# schematics.net
KiCad netlist of a schematic drawn in EAGLE
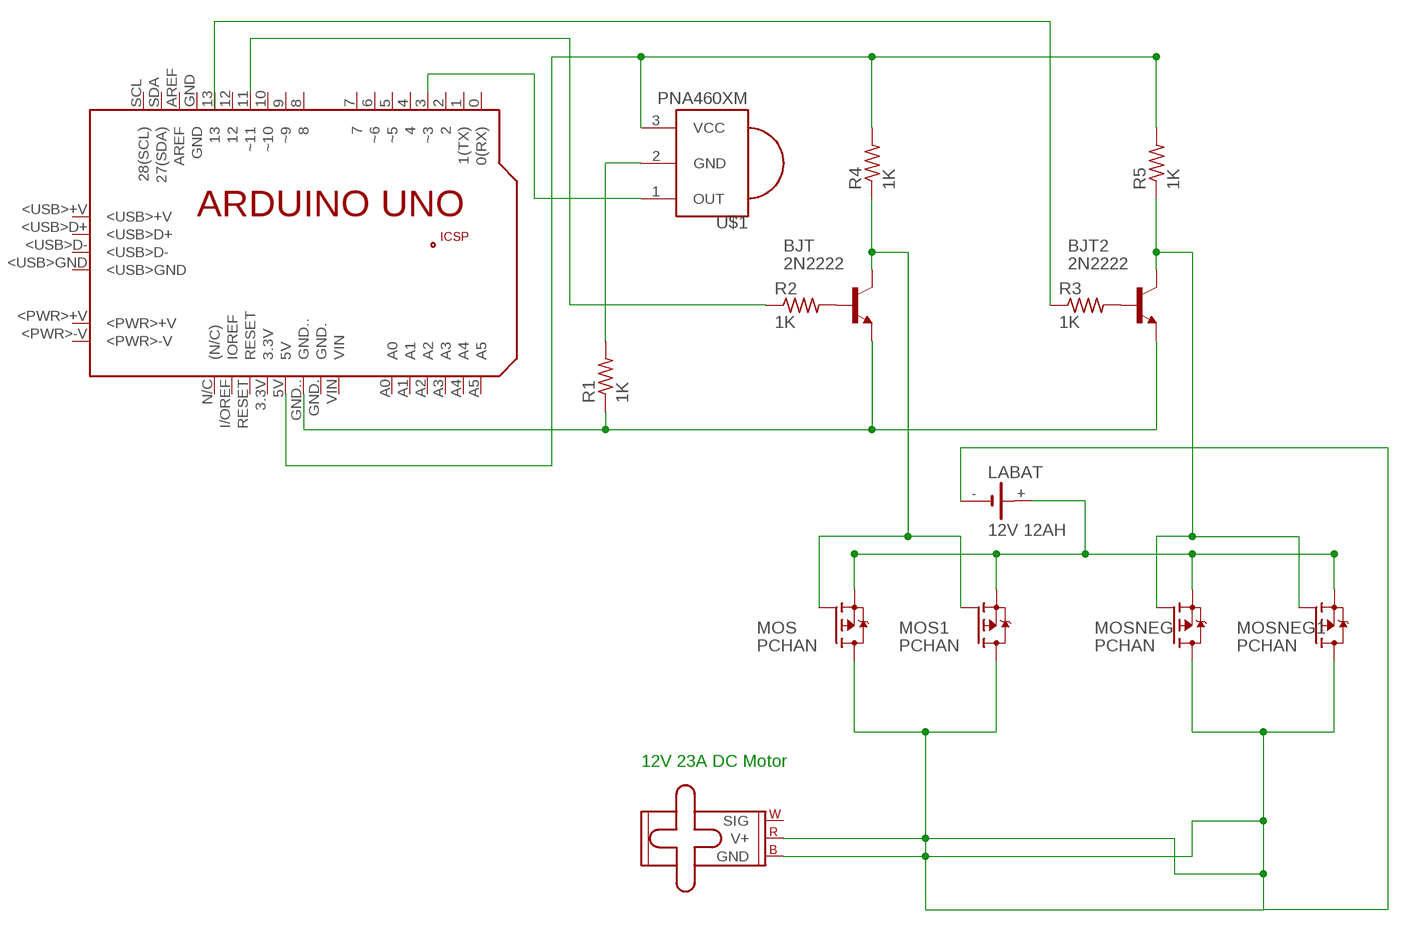
[diagram p0: schematic, sheet 1]

(export (version "E")
  (design (tool "Eeschema 10.0.6"))
  (components
    (comp (ref "BJT")
      (value "2N2222")
      (footprint "eagle-import:TO92-EBC-OVAL")
      (libsource (lib "eagle-import") (part "2N2222"))
    )
    (comp (ref "BJT2")
      (value "2N2222")
      (footprint "eagle-import:TO92-EBC-OVAL")
      (libsource (lib "eagle-import") (part "2N2222"))
    )
    (comp (ref "DCMOTOR")
      (value "12V 23A")
      (footprint "eagle-import:1X03")
      (libsource (lib "eagle-import") (part "SMALL_SERVO"))
    )
    (comp (ref "LABAT")
      (value "12V 12AH")
      (footprint "eagle-import:SL-160AA_PR")
      (libsource (lib "eagle-import") (part "SL-160AA/PR"))
    )
    (comp (ref "MOS")
      (value "PCHAN")
      (footprint "eagle-import:TO252")
      (libsource (lib "eagle-import") (part "FDD4141TO252"))
    )
    (comp (ref "MOS1")
      (value "PCHAN")
      (footprint "eagle-import:TO252")
      (libsource (lib "eagle-import") (part "FDD4141TO252"))
    )
    (comp (ref "MOSNEG")
      (value "PCHAN")
      (footprint "eagle-import:TO252")
      (libsource (lib "eagle-import") (part "FDD4141TO252"))
    )
    (comp (ref "MOSNEG1")
      (value "PCHAN")
      (footprint "eagle-import:TO252")
      (libsource (lib "eagle-import") (part "FDD4141TO252"))
    )
    (comp (ref "PCB1")
      (value "ARDUINO_UNO")
      (footprint "eagle-import:ARDUINO_UNO")
      (libsource (lib "eagle-import") (part "ARDUINO_UNO"))
    )
    (comp (ref "R1")
      (value "1K")
      (footprint "eagle-import:0207_7")
      (libsource (lib "eagle-import") (part "R-US_0207/7"))
    )
    (comp (ref "R2")
      (value "1K")
      (footprint "eagle-import:0207_7")
      (libsource (lib "eagle-import") (part "R-US_0207/7"))
    )
    (comp (ref "R3")
      (value "1K")
      (footprint "eagle-import:0207_7")
      (libsource (lib "eagle-import") (part "R-US_0207/7"))
    )
    (comp (ref "R4")
      (value "1K")
      (footprint "eagle-import:0207_7")
      (libsource (lib "eagle-import") (part "R-US_0207/7"))
    )
    (comp (ref "R5")
      (value "1K")
      (footprint "eagle-import:0207_7")
      (libsource (lib "eagle-import") (part "R-US_0207/7"))
    )
    (comp (ref "U$1")
      (value "PNA460XM")
      (footprint "eagle-import:PNA460XM")
      (libsource (lib "eagle-import") (part "PNA460XM"))
    )
  )
  (nets
    (net (code "1") (name "Net-(BJT-PadB)") (class "Default")
      (node (ref "BJT") (pin "B") (pinfunction "B_B") (pintype "passive"))
      (node (ref "R2") (pin "2") (pinfunction "2_2") (pintype "passive"))
    )
    (net (code "2") (name "Net-(BJT-PadE)") (class "Default")
      (node (ref "BJT") (pin "E") (pinfunction "E_E") (pintype "passive"))
      (node (ref "BJT2") (pin "E") (pinfunction "E_E") (pintype "passive"))
      (node (ref "PCB1") (pin "GND..") (pinfunction "GND.._GND..") (pintype "bidirectional"))
      (node (ref "R1") (pin "1") (pinfunction "1_1") (pintype "passive"))
    )
    (net (code "3") (name "Net-(BJT2-PadB)") (class "Default")
      (node (ref "BJT2") (pin "B") (pinfunction "B_B") (pintype "passive"))
      (node (ref "R3") (pin "2") (pinfunction "2_2") (pintype "passive"))
    )
    (net (code "4") (name "Net-(DCMOTOR-GND)") (class "Default")
      (node (ref "DCMOTOR") (pin "2") (pinfunction "V+_2") (pintype "bidirectional"))
      (node (ref "DCMOTOR") (pin "3") (pinfunction "GND_3") (pintype "bidirectional"))
      (node (ref "LABAT") (pin "-") (pinfunction "-_-") (pintype "passive"))
      (node (ref "MOS") (pin "3") (pinfunction "D_3") (pintype "passive"))
      (node (ref "MOS1") (pin "3") (pinfunction "D_3") (pintype "passive"))
      (node (ref "MOSNEG") (pin "3") (pinfunction "D_3") (pintype "passive"))
      (node (ref "MOSNEG1") (pin "3") (pinfunction "D_3") (pintype "passive"))
    )
    (net (code "5") (name "Net-(MOS-G)") (class "Default")
      (node (ref "BJT") (pin "C") (pinfunction "C_C") (pintype "passive"))
      (node (ref "MOS") (pin "1") (pinfunction "G_1") (pintype "passive"))
      (node (ref "MOS1") (pin "1") (pinfunction "G_1") (pintype "passive"))
      (node (ref "R4") (pin "1") (pinfunction "1_1") (pintype "passive"))
    )
    (net (code "6") (name "Net-(MOS-S)") (class "Default")
      (node (ref "LABAT") (pin "+") (pinfunction "+_+") (pintype "passive"))
      (node (ref "MOS") (pin "2") (pinfunction "S_2") (pintype "passive"))
      (node (ref "MOS1") (pin "2") (pinfunction "S_2") (pintype "passive"))
      (node (ref "MOSNEG") (pin "2") (pinfunction "S_2") (pintype "passive"))
      (node (ref "MOSNEG1") (pin "2") (pinfunction "S_2") (pintype "passive"))
    )
    (net (code "7") (name "Net-(MOSNEG-G)") (class "Default")
      (node (ref "BJT2") (pin "C") (pinfunction "C_C") (pintype "passive"))
      (node (ref "MOSNEG") (pin "1") (pinfunction "G_1") (pintype "passive"))
      (node (ref "MOSNEG1") (pin "1") (pinfunction "G_1") (pintype "passive"))
      (node (ref "R5") (pin "1") (pinfunction "1_1") (pintype "passive"))
    )
    (net (code "8") (name "Net-(PCB1-~{3})") (class "Default")
      (node (ref "PCB1") (pin "3") (pinfunction "~{3}_3") (pintype "bidirectional"))
      (node (ref "U$1") (pin "1") (pinfunction "OUT_1") (pintype "output"))
    )
    (net (code "9") (name "Net-(PCB1-~{11})") (class "Default")
      (node (ref "PCB1") (pin "11") (pinfunction "~{11}_11") (pintype "bidirectional"))
      (node (ref "R2") (pin "1") (pinfunction "1_1") (pintype "passive"))
    )
    (net (code "10") (name "Net-(U$1-GND)") (class "Default")
      (node (ref "R1") (pin "2") (pinfunction "2_2") (pintype "passive"))
      (node (ref "U$1") (pin "2") (pinfunction "GND_2") (pintype "power_in"))
    )
    (net (code "11") (name "Net-(U$1-VCC)") (class "Default")
      (node (ref "PCB1") (pin "5V") (pinfunction "5V_5V") (pintype "bidirectional"))
      (node (ref "R4") (pin "2") (pinfunction "2_2") (pintype "passive"))
      (node (ref "R5") (pin "2") (pinfunction "2_2") (pintype "passive"))
      (node (ref "U$1") (pin "3") (pinfunction "VCC_3") (pintype "power_in"))
    )
    (net (code "12") (name "unconnected-(DCMOTOR-SIG-Pad1)") (class "Default")
      (node (ref "DCMOTOR") (pin "1") (pinfunction "SIG_1") (pintype "bidirectional"))
    )
    (net (code "13") (name "unconnected-(PCB1-(N{slash}C)-PadN{slash}C)") (class "Default")
      (node (ref "PCB1") (pin "N/C") (pinfunction "(N/C)_N/C") (pintype "bidirectional"))
    )
    (net (code "14") (name "unconnected-(PCB1-0(RX)-Pad0)") (class "Default")
      (node (ref "PCB1") (pin "0") (pinfunction "0(RX)_0") (pintype "bidirectional"))
    )
    (net (code "15") (name "unconnected-(PCB1-1(TX)-Pad1)") (class "Default")
      (node (ref "PCB1") (pin "1") (pinfunction "1(TX)_1") (pintype "bidirectional"))
    )
    (net (code "16") (name "unconnected-(PCB1-27(SDA)-PadSDA)") (class "Default")
      (node (ref "PCB1") (pin "SDA") (pinfunction "27(SDA)_SDA") (pintype "bidirectional"))
    )
    (net (code "17") (name "unconnected-(PCB1-28(SCL)-PadSCL)") (class "Default")
      (node (ref "PCB1") (pin "SCL") (pinfunction "28(SCL)_SCL") (pintype "bidirectional"))
    )
    (net (code "18") (name "unconnected-(PCB1-IOREF-PadI{slash}OREF)") (class "Default")
      (node (ref "PCB1") (pin "I/OREF") (pinfunction "IOREF_I/OREF") (pintype "bidirectional"))
    )
    (net (code "19") (name "unconnected-(PCB1-Pad+5V)") (class "Default")
      (node (ref "PCB1") (pin "+5V") (pinfunction "+5V_+5V") (pintype "bidirectional"))
    )
    (net (code "20") (name "unconnected-(PCB1-Pad2)") (class "Default")
      (node (ref "PCB1") (pin "2") (pinfunction "2_2") (pintype "bidirectional"))
    )
    (net (code "21") (name "unconnected-(PCB1-Pad3.3V)") (class "Default")
      (node (ref "PCB1") (pin "3.3V") (pinfunction "3.3V_3.3V") (pintype "bidirectional"))
    )
    (net (code "22") (name "unconnected-(PCB1-Pad4)") (class "Default")
      (node (ref "PCB1") (pin "4") (pinfunction "4_4") (pintype "bidirectional"))
    )
    (net (code "23") (name "unconnected-(PCB1-Pad7)") (class "Default")
      (node (ref "PCB1") (pin "7") (pinfunction "7_7") (pintype "bidirectional"))
    )
    (net (code "24") (name "unconnected-(PCB1-Pad8)") (class "Default")
      (node (ref "PCB1") (pin "8") (pinfunction "8_8") (pintype "bidirectional"))
    )
    (net (code "25") (name "unconnected-(PCB1-Pad12)") (class "Default")
      (node (ref "PCB1") (pin "12") (pinfunction "12_12") (pintype "bidirectional"))
    )
    (net (code "26") (name "unconnected-(PCB1-Pad13)") (class "Default")
      (node (ref "PCB1") (pin "13") (pinfunction "13_13") (pintype "bidirectional"))
    )
    (net (code "27") (name "unconnected-(PCB1-Pad<PWR>+V)") (class "Default")
      (node (ref "PCB1") (pin "<PWR>+V") (pinfunction "<PWR>+V_<PWR>+V") (pintype "bidirectional"))
    )
    (net (code "28") (name "unconnected-(PCB1-Pad<PWR>-V)") (class "Default")
      (node (ref "PCB1") (pin "<PWR>-V") (pinfunction "<PWR>-V_<PWR>-V") (pintype "bidirectional"))
    )
    (net (code "29") (name "unconnected-(PCB1-Pad<USB>+V)") (class "Default")
      (node (ref "PCB1") (pin "<USB>+V") (pinfunction "<USB>+V_<USB>+V") (pintype "bidirectional"))
    )
    (net (code "30") (name "unconnected-(PCB1-Pad<USB>D+)") (class "Default")
      (node (ref "PCB1") (pin "<USB>D+") (pinfunction "<USB>D+_<USB>D+") (pintype "bidirectional"))
    )
    (net (code "31") (name "unconnected-(PCB1-Pad<USB>D-)") (class "Default")
      (node (ref "PCB1") (pin "<USB>D-") (pinfunction "<USB>D-_<USB>D-") (pintype "bidirectional"))
    )
    (net (code "32") (name "unconnected-(PCB1-Pad<USB>GND)") (class "Default")
      (node (ref "PCB1") (pin "<USB>GND") (pinfunction "<USB>GND_<USB>GND") (pintype "bidirectional"))
    )
    (net (code "33") (name "unconnected-(PCB1-PadA0)") (class "Default")
      (node (ref "PCB1") (pin "A0") (pinfunction "A0_A0") (pintype "bidirectional"))
    )
    (net (code "34") (name "unconnected-(PCB1-PadA1)") (class "Default")
      (node (ref "PCB1") (pin "A1") (pinfunction "A1_A1") (pintype "bidirectional"))
    )
    (net (code "35") (name "unconnected-(PCB1-PadA2)") (class "Default")
      (node (ref "PCB1") (pin "A2") (pinfunction "A2_A2") (pintype "bidirectional"))
    )
    (net (code "36") (name "unconnected-(PCB1-PadA3)") (class "Default")
      (node (ref "PCB1") (pin "A3") (pinfunction "A3_A3") (pintype "bidirectional"))
    )
    (net (code "37") (name "unconnected-(PCB1-PadA4)") (class "Default")
      (node (ref "PCB1") (pin "A4") (pinfunction "A4_A4") (pintype "bidirectional"))
    )
    (net (code "38") (name "unconnected-(PCB1-PadA5)") (class "Default")
      (node (ref "PCB1") (pin "A5") (pinfunction "A5_A5") (pintype "bidirectional"))
    )
    (net (code "39") (name "unconnected-(PCB1-PadAREF)") (class "Default")
      (node (ref "PCB1") (pin "AREF") (pinfunction "AREF_AREF") (pintype "bidirectional"))
    )
    (net (code "40") (name "unconnected-(PCB1-PadGND)") (class "Default")
      (node (ref "PCB1") (pin "GND") (pinfunction "GND_GND") (pintype "bidirectional"))
    )
    (net (code "41") (name "unconnected-(PCB1-PadGND.)") (class "Default")
      (node (ref "PCB1") (pin "GND.") (pinfunction "GND._GND.") (pintype "bidirectional"))
    )
    (net (code "42") (name "unconnected-(PCB1-PadGND_)") (class "Default")
      (node (ref "PCB1") (pin "GND_") (pinfunction "GND__GND_") (pintype "bidirectional"))
    )
    (net (code "43") (name "unconnected-(PCB1-PadMISO)") (class "Default")
      (node (ref "PCB1") (pin "MISO") (pinfunction "MISO_MISO") (pintype "bidirectional"))
    )
    (net (code "44") (name "unconnected-(PCB1-PadMOSI)") (class "Default")
      (node (ref "PCB1") (pin "MOSI") (pinfunction "MOSI_MOSI") (pintype "bidirectional"))
    )
    (net (code "45") (name "unconnected-(PCB1-PadRESET)") (class "Default")
      (node (ref "PCB1") (pin "RESET") (pinfunction "RESET_RESET") (pintype "bidirectional"))
    )
    (net (code "46") (name "unconnected-(PCB1-PadRESET.)") (class "Default")
      (node (ref "PCB1") (pin "RESET.") (pinfunction "RESET._RESET.") (pintype "bidirectional"))
    )
    (net (code "47") (name "unconnected-(PCB1-PadSCK)") (class "Default")
      (node (ref "PCB1") (pin "SCK") (pinfunction "SCK_SCK") (pintype "bidirectional"))
    )
    (net (code "48") (name "unconnected-(PCB1-PadVIN)") (class "Default")
      (node (ref "PCB1") (pin "VIN") (pinfunction "VIN_VIN") (pintype "bidirectional"))
    )
    (net (code "49") (name "unconnected-(PCB1-~{5}-Pad5)") (class "Default")
      (node (ref "PCB1") (pin "5") (pinfunction "~{5}_5") (pintype "bidirectional"))
    )
    (net (code "50") (name "unconnected-(PCB1-~{6}-Pad6)") (class "Default")
      (node (ref "PCB1") (pin "6") (pinfunction "~{6}_6") (pintype "bidirectional"))
    )
    (net (code "51") (name "unconnected-(PCB1-~{9}-Pad9)") (class "Default")
      (node (ref "PCB1") (pin "9") (pinfunction "~{9}_9") (pintype "bidirectional"))
    )
    (net (code "52") (name "unconnected-(PCB1-~{10}-Pad10)") (class "Default")
      (node (ref "PCB1") (pin "10") (pinfunction "~{10}_10") (pintype "bidirectional"))
    )
    (net (code "53") (name "unconnected-(R3-Pad1)") (class "Default")
      (node (ref "R3") (pin "1") (pinfunction "1_1") (pintype "passive"))
    )
  )
)
